# joystick_controller.net
KiCad netlist of a schematic drawn in EAGLE
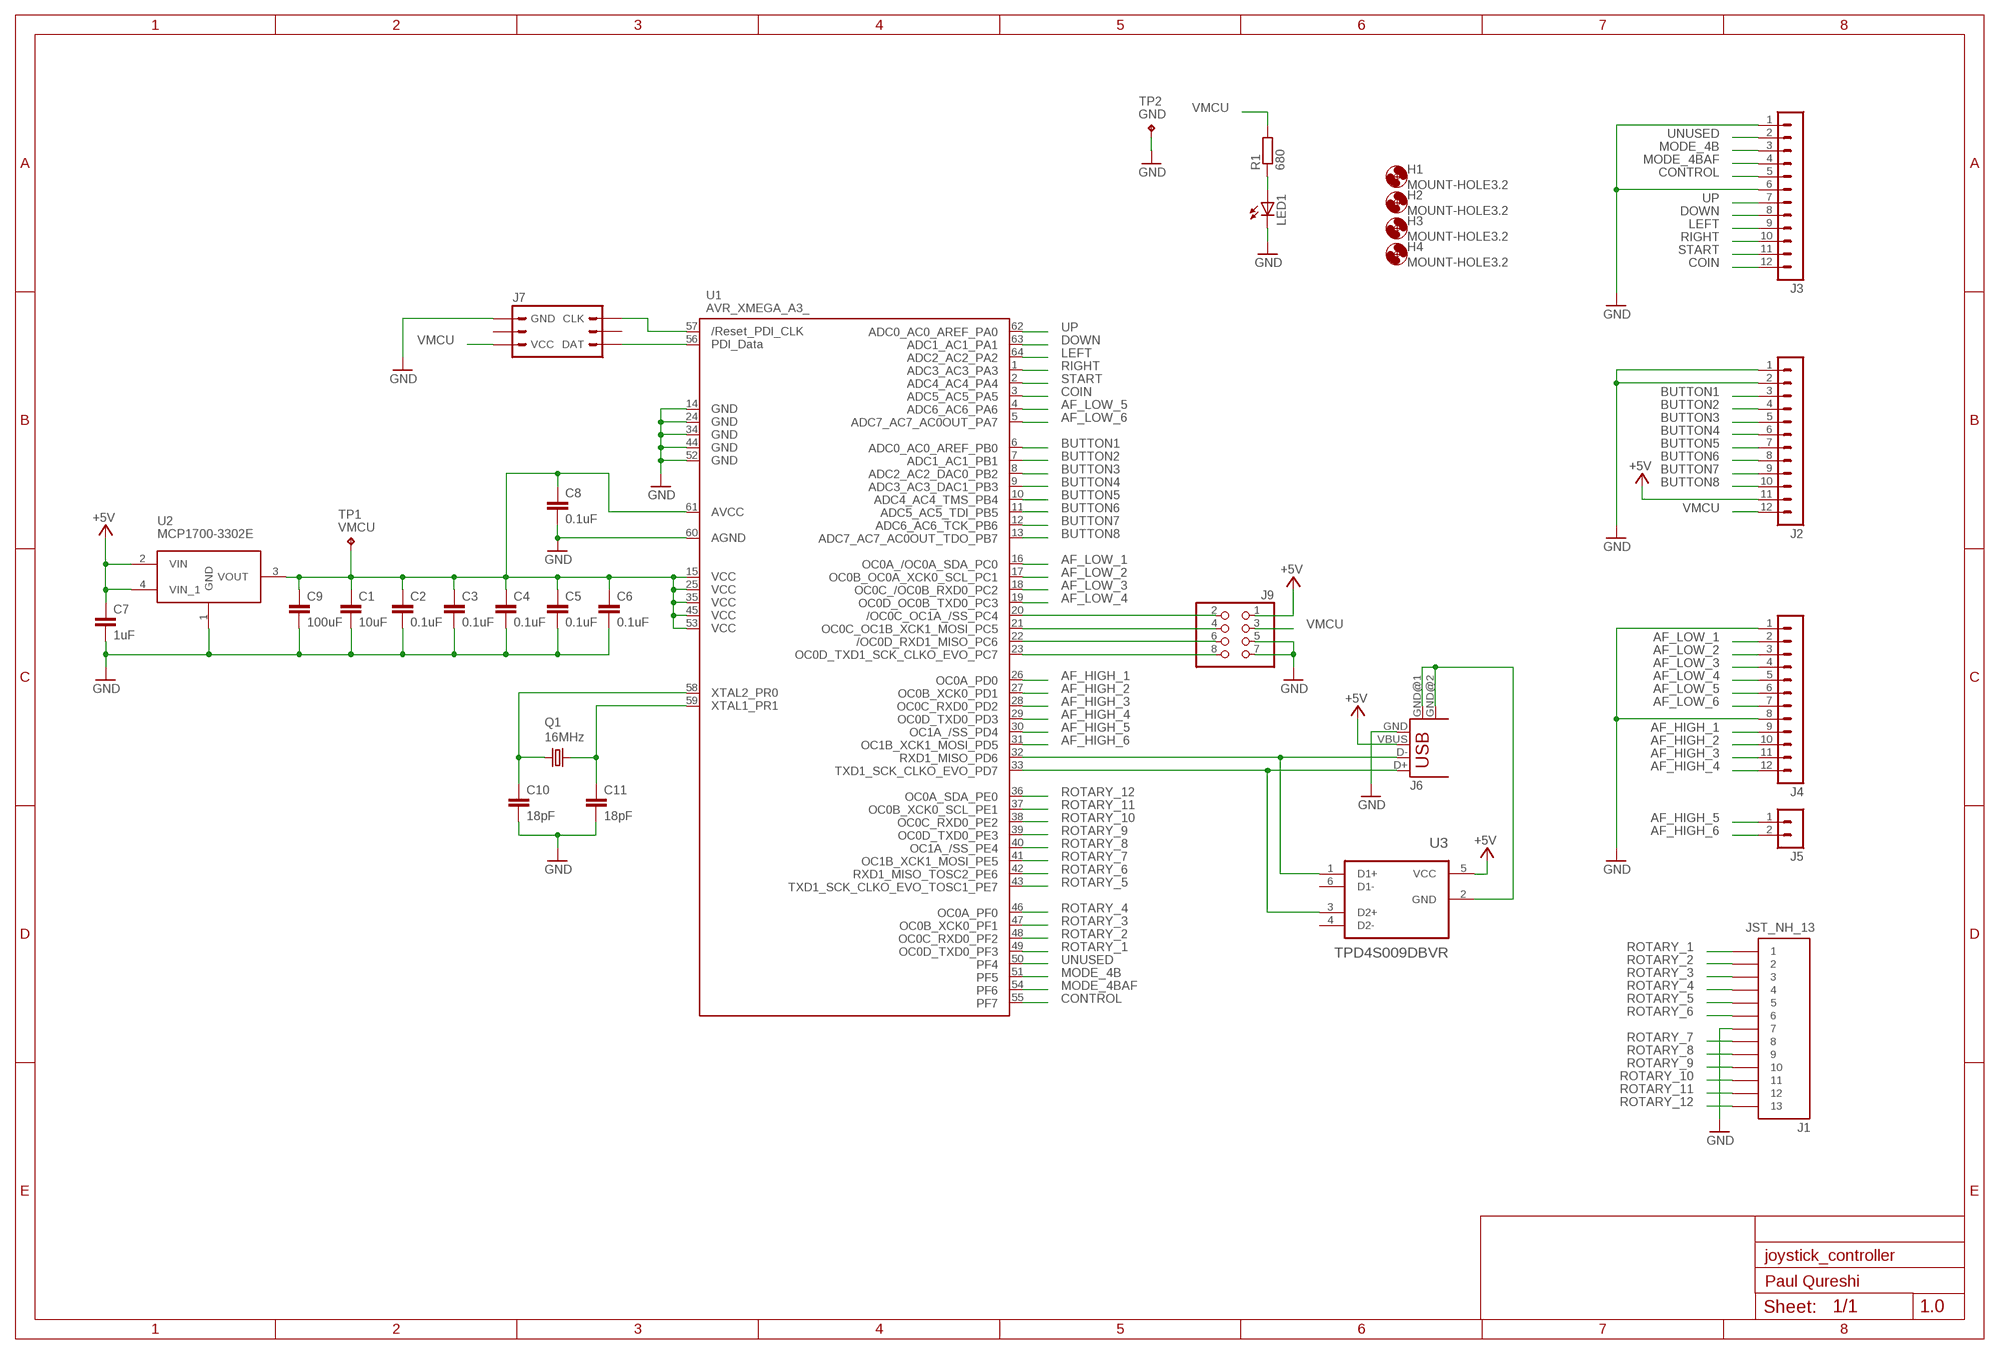
[diagram p0: schematic, sheet 1]

(export (version "E")
  (design (tool "Eeschema 10.0.6"))
  (components
    (comp (ref "C1")
      (value "10uF")
      (footprint "eagle-import:C0805")
      (libsource (lib "eagle-import") (part "C-EUC0805"))
    )
    (comp (ref "C2")
      (value "0.1uF")
      (footprint "eagle-import:C0805")
      (libsource (lib "eagle-import") (part "C-EUC0805"))
    )
    (comp (ref "C3")
      (value "0.1uF")
      (footprint "eagle-import:C0805")
      (libsource (lib "eagle-import") (part "C-EUC0805"))
    )
    (comp (ref "C4")
      (value "0.1uF")
      (footprint "eagle-import:C0805")
      (libsource (lib "eagle-import") (part "C-EUC0805"))
    )
    (comp (ref "C5")
      (value "0.1uF")
      (footprint "eagle-import:C0805")
      (libsource (lib "eagle-import") (part "C-EUC0805"))
    )
    (comp (ref "C6")
      (value "0.1uF")
      (footprint "eagle-import:C0805")
      (libsource (lib "eagle-import") (part "C-EUC0805"))
    )
    (comp (ref "C7")
      (value "1uF")
      (footprint "eagle-import:C0805")
      (libsource (lib "eagle-import") (part "C-EUC0805"))
    )
    (comp (ref "C8")
      (value "0.1uF")
      (footprint "eagle-import:C0805")
      (libsource (lib "eagle-import") (part "C-EUC0805"))
    )
    (comp (ref "C9")
      (value "100uF")
      (footprint "eagle-import:C1206")
      (libsource (lib "eagle-import") (part "C-EUC1206"))
    )
    (comp (ref "C10")
      (value "18pF")
      (footprint "eagle-import:C0805")
      (libsource (lib "eagle-import") (part "C-EUC0805"))
    )
    (comp (ref "C11")
      (value "18pF")
      (footprint "eagle-import:C0805")
      (libsource (lib "eagle-import") (part "C-EUC0805"))
    )
    (comp (ref "H1")
      (value "MOUNT-HOLE3.2")
      (footprint "eagle-import:3,2")
      (libsource (lib "eagle-import") (part "MOUNT-HOLE3.2"))
    )
    (comp (ref "H2")
      (value "MOUNT-HOLE3.2")
      (footprint "eagle-import:3,2")
      (libsource (lib "eagle-import") (part "MOUNT-HOLE3.2"))
    )
    (comp (ref "H3")
      (value "MOUNT-HOLE3.2")
      (footprint "eagle-import:3,2")
      (libsource (lib "eagle-import") (part "MOUNT-HOLE3.2"))
    )
    (comp (ref "H4")
      (value "MOUNT-HOLE3.2")
      (footprint "eagle-import:3,2")
      (libsource (lib "eagle-import") (part "MOUNT-HOLE3.2"))
    )
    (comp (ref "J1")
      (value "JST_NH_13")
      (footprint "eagle-import:JST_NH_13_RA")
      (libsource (lib "eagle-import") (part "JST_NH_13"))
    )
    (comp (ref "J2")
      (value "CON-3.5TERM-12")
      (footprint "eagle-import:CON-3.5TERM-12")
      (libsource (lib "eagle-import") (part "CON-3.5TERM-12"))
    )
    (comp (ref "J3")
      (value "CON-3.5TERM-12")
      (footprint "eagle-import:CON-3.5TERM-12")
      (libsource (lib "eagle-import") (part "CON-3.5TERM-12"))
    )
    (comp (ref "J4")
      (value "CON-3.5TERM-12")
      (footprint "eagle-import:CON-3.5TERM-12")
      (libsource (lib "eagle-import") (part "CON-3.5TERM-12"))
    )
    (comp (ref "J5")
      (value "CON-3.5TERM-2")
      (footprint "eagle-import:CON-3.5TERM-2")
      (libsource (lib "eagle-import") (part "CON-3.5TERM-2"))
    )
    (comp (ref "J6")
      (value "USB-B-H")
      (footprint "eagle-import:USB-B-H")
      (libsource (lib "eagle-import") (part "USB-B-H"))
    )
    (comp (ref "J7")
      (value "PDI_HEADER")
      (footprint "eagle-import:MA03-2")
      (libsource (lib "eagle-import") (part "PDI_HEADER"))
    )
    (comp (ref "J9")
      (value "PINHD-2X4")
      (footprint "eagle-import:2X04")
      (libsource (lib "eagle-import") (part "PINHD-2X4"))
    )
    (comp (ref "LED1")
      (value "LEDCHIP-LED0805")
      (footprint "eagle-import:CHIP-LED0805")
      (libsource (lib "eagle-import") (part "LEDCHIP-LED0805"))
    )
    (comp (ref "Q1")
      (value "16MHz")
      (footprint "eagle-import:HC49_S")
      (libsource (lib "eagle-import") (part "CRYSTALHC49S"))
    )
    (comp (ref "R1")
      (value "680")
      (footprint "eagle-import:R0805")
      (libsource (lib "eagle-import") (part "R-EU_R0805"))
    )
    (comp (ref "TP1")
      (value "VMCU")
      (footprint "eagle-import:HARWIN-S1751-46")
      (libsource (lib "eagle-import") (part "TEST_POINTS1751"))
    )
    (comp (ref "TP2")
      (value "GND")
      (footprint "eagle-import:HARWIN-S1751-46")
      (libsource (lib "eagle-import") (part "TEST_POINTS1751"))
    )
    (comp (ref "U1")
      (value "AVR_XMEGA_A3_")
      (footprint "eagle-import:TQFP64")
      (libsource (lib "eagle-import") (part "AVR_XMEGA_A3_"))
    )
    (comp (ref "U2")
      (value "MCP1700-3302E")
      (footprint "eagle-import:SOT150P400X160-4N")
      (fields (field (name "MPN") "MCP1700T-3302E/MB"))
      (libsource (lib "eagle-import") (part "MCP17-MCP1700T-3302E/MB"))
    )
    (comp (ref "U3")
      (value "TPD4S009DBVR")
      (footprint "eagle-import:SOT95P280X145-6N")
      (libsource (lib "eagle-import") (part "TPD4S009DBVR"))
    )
  )
  (nets
    (net (code "1") (name "+5V") (class "Default")
      (node (ref "C7") (pin "1") (pinfunction "1_1") (pintype "passive"))
      (node (ref "J2") (pin "11") (pinfunction "11_11") (pintype "passive"))
      (node (ref "J6") (pin "VBUS") (pinfunction "VBUS_VBUS") (pintype "bidirectional"))
      (node (ref "J9") (pin "1") (pinfunction "1_1") (pintype "passive"))
      (node (ref "U2") (pin "2") (pinfunction "VIN_2") (pintype "input"))
      (node (ref "U2") (pin "4") (pinfunction "VIN_1_4") (pintype "input"))
      (node (ref "U3") (pin "5") (pinfunction "VCC_5") (pintype "power_in"))
    )
    (net (code "2") (name "/AF_HIGH_1") (class "Default")
      (node (ref "J4") (pin "9") (pinfunction "9_9") (pintype "passive"))
      (node (ref "U1") (pin "26") (pinfunction "PD0_26") (pintype "bidirectional"))
    )
    (net (code "3") (name "/AF_HIGH_2") (class "Default")
      (node (ref "J4") (pin "10") (pinfunction "10_10") (pintype "passive"))
      (node (ref "U1") (pin "27") (pinfunction "PD1_27") (pintype "bidirectional"))
    )
    (net (code "4") (name "/AF_HIGH_3") (class "Default")
      (node (ref "J4") (pin "11") (pinfunction "11_11") (pintype "passive"))
      (node (ref "U1") (pin "28") (pinfunction "PD2_28") (pintype "bidirectional"))
    )
    (net (code "5") (name "/AF_HIGH_4") (class "Default")
      (node (ref "J4") (pin "12") (pinfunction "12_12") (pintype "passive"))
      (node (ref "U1") (pin "29") (pinfunction "PD3_29") (pintype "bidirectional"))
    )
    (net (code "6") (name "/AF_HIGH_5") (class "Default")
      (node (ref "J5") (pin "1") (pinfunction "1_1") (pintype "passive"))
      (node (ref "U1") (pin "30") (pinfunction "PD4_30") (pintype "bidirectional"))
    )
    (net (code "7") (name "/AF_HIGH_6") (class "Default")
      (node (ref "J5") (pin "2") (pinfunction "2_2") (pintype "passive"))
      (node (ref "U1") (pin "31") (pinfunction "PD5_31") (pintype "bidirectional"))
    )
    (net (code "8") (name "/AF_LOW_1") (class "Default")
      (node (ref "J4") (pin "2") (pinfunction "2_2") (pintype "passive"))
      (node (ref "U1") (pin "16") (pinfunction "PC0_16") (pintype "bidirectional"))
    )
    (net (code "9") (name "/AF_LOW_2") (class "Default")
      (node (ref "J4") (pin "3") (pinfunction "3_3") (pintype "passive"))
      (node (ref "U1") (pin "17") (pinfunction "PC1_17") (pintype "bidirectional"))
    )
    (net (code "10") (name "/AF_LOW_3") (class "Default")
      (node (ref "J4") (pin "4") (pinfunction "4_4") (pintype "passive"))
      (node (ref "U1") (pin "18") (pinfunction "PC2_18") (pintype "bidirectional"))
    )
    (net (code "11") (name "/AF_LOW_4") (class "Default")
      (node (ref "J4") (pin "5") (pinfunction "5_5") (pintype "passive"))
      (node (ref "U1") (pin "19") (pinfunction "PC3_19") (pintype "bidirectional"))
    )
    (net (code "12") (name "/AF_LOW_5") (class "Default")
      (node (ref "J4") (pin "6") (pinfunction "6_6") (pintype "passive"))
      (node (ref "U1") (pin "4") (pinfunction "PA6_4") (pintype "bidirectional"))
    )
    (net (code "13") (name "/AF_LOW_6") (class "Default")
      (node (ref "J4") (pin "7") (pinfunction "7_7") (pintype "passive"))
      (node (ref "U1") (pin "5") (pinfunction "PA7_5") (pintype "bidirectional"))
    )
    (net (code "14") (name "/BUTTON1") (class "Default")
      (node (ref "J2") (pin "3") (pinfunction "3_3") (pintype "passive"))
      (node (ref "U1") (pin "6") (pinfunction "PB0_6") (pintype "bidirectional"))
    )
    (net (code "15") (name "/BUTTON2") (class "Default")
      (node (ref "J2") (pin "4") (pinfunction "4_4") (pintype "passive"))
      (node (ref "U1") (pin "7") (pinfunction "PB1_7") (pintype "bidirectional"))
    )
    (net (code "16") (name "/BUTTON3") (class "Default")
      (node (ref "J2") (pin "5") (pinfunction "5_5") (pintype "passive"))
      (node (ref "U1") (pin "8") (pinfunction "PB2_8") (pintype "bidirectional"))
    )
    (net (code "17") (name "/BUTTON4") (class "Default")
      (node (ref "J2") (pin "6") (pinfunction "6_6") (pintype "passive"))
      (node (ref "U1") (pin "9") (pinfunction "PB3_9") (pintype "bidirectional"))
    )
    (net (code "18") (name "/BUTTON5") (class "Default")
      (node (ref "J2") (pin "7") (pinfunction "7_7") (pintype "passive"))
      (node (ref "U1") (pin "10") (pinfunction "PB4_10") (pintype "bidirectional"))
    )
    (net (code "19") (name "/BUTTON6") (class "Default")
      (node (ref "J2") (pin "8") (pinfunction "8_8") (pintype "passive"))
      (node (ref "U1") (pin "11") (pinfunction "PB5_11") (pintype "bidirectional"))
    )
    (net (code "20") (name "/BUTTON7") (class "Default")
      (node (ref "J2") (pin "9") (pinfunction "9_9") (pintype "passive"))
      (node (ref "U1") (pin "12") (pinfunction "PB6_12") (pintype "bidirectional"))
    )
    (net (code "21") (name "/BUTTON8") (class "Default")
      (node (ref "J2") (pin "10") (pinfunction "10_10") (pintype "passive"))
      (node (ref "U1") (pin "13") (pinfunction "PB7_13") (pintype "bidirectional"))
    )
    (net (code "22") (name "/COIN") (class "Default")
      (node (ref "J3") (pin "12") (pinfunction "12_12") (pintype "passive"))
      (node (ref "U1") (pin "3") (pinfunction "PA5_3") (pintype "bidirectional"))
    )
    (net (code "23") (name "/CONTROL") (class "Default")
      (node (ref "J3") (pin "5") (pinfunction "5_5") (pintype "passive"))
      (node (ref "U1") (pin "55") (pinfunction "PF7_55") (pintype "bidirectional"))
    )
    (net (code "24") (name "/DOWN") (class "Default")
      (node (ref "J3") (pin "8") (pinfunction "8_8") (pintype "passive"))
      (node (ref "U1") (pin "63") (pinfunction "PA1_63") (pintype "bidirectional"))
    )
    (net (code "25") (name "/LEFT") (class "Default")
      (node (ref "J3") (pin "9") (pinfunction "9_9") (pintype "passive"))
      (node (ref "U1") (pin "64") (pinfunction "PA2_64") (pintype "bidirectional"))
    )
    (net (code "26") (name "/MODE_4B") (class "Default")
      (node (ref "J3") (pin "3") (pinfunction "3_3") (pintype "passive"))
      (node (ref "U1") (pin "51") (pinfunction "PF5_51") (pintype "bidirectional"))
    )
    (net (code "27") (name "/MODE_4BAF") (class "Default")
      (node (ref "J3") (pin "4") (pinfunction "4_4") (pintype "passive"))
      (node (ref "U1") (pin "54") (pinfunction "PF6_54") (pintype "bidirectional"))
    )
    (net (code "28") (name "/RIGHT") (class "Default")
      (node (ref "J3") (pin "10") (pinfunction "10_10") (pintype "passive"))
      (node (ref "U1") (pin "1") (pinfunction "PA3_1") (pintype "bidirectional"))
    )
    (net (code "29") (name "/ROTARY_1") (class "Default")
      (node (ref "J1") (pin "1") (pinfunction "1_1") (pintype "passive"))
      (node (ref "U1") (pin "49") (pinfunction "PF3_49") (pintype "bidirectional"))
    )
    (net (code "30") (name "/ROTARY_2") (class "Default")
      (node (ref "J1") (pin "2") (pinfunction "2_2") (pintype "passive"))
      (node (ref "U1") (pin "48") (pinfunction "PF2_48") (pintype "bidirectional"))
    )
    (net (code "31") (name "/ROTARY_3") (class "Default")
      (node (ref "J1") (pin "3") (pinfunction "3_3") (pintype "passive"))
      (node (ref "U1") (pin "47") (pinfunction "PF1_47") (pintype "bidirectional"))
    )
    (net (code "32") (name "/ROTARY_4") (class "Default")
      (node (ref "J1") (pin "4") (pinfunction "4_4") (pintype "passive"))
      (node (ref "U1") (pin "46") (pinfunction "PF0_46") (pintype "bidirectional"))
    )
    (net (code "33") (name "/ROTARY_5") (class "Default")
      (node (ref "J1") (pin "5") (pinfunction "5_5") (pintype "passive"))
      (node (ref "U1") (pin "43") (pinfunction "PE7_43") (pintype "bidirectional"))
    )
    (net (code "34") (name "/ROTARY_6") (class "Default")
      (node (ref "J1") (pin "6") (pinfunction "6_6") (pintype "passive"))
      (node (ref "U1") (pin "42") (pinfunction "PE6_42") (pintype "bidirectional"))
    )
    (net (code "35") (name "/ROTARY_7") (class "Default")
      (node (ref "J1") (pin "8") (pinfunction "8_8") (pintype "passive"))
      (node (ref "U1") (pin "41") (pinfunction "PE5_41") (pintype "bidirectional"))
    )
    (net (code "36") (name "/ROTARY_8") (class "Default")
      (node (ref "J1") (pin "9") (pinfunction "9_9") (pintype "passive"))
      (node (ref "U1") (pin "40") (pinfunction "PE4_40") (pintype "bidirectional"))
    )
    (net (code "37") (name "/ROTARY_9") (class "Default")
      (node (ref "J1") (pin "10") (pinfunction "10_10") (pintype "passive"))
      (node (ref "U1") (pin "39") (pinfunction "PE3_39") (pintype "bidirectional"))
    )
    (net (code "38") (name "/ROTARY_10") (class "Default")
      (node (ref "J1") (pin "11") (pinfunction "11_11") (pintype "passive"))
      (node (ref "U1") (pin "38") (pinfunction "PE2_38") (pintype "bidirectional"))
    )
    (net (code "39") (name "/ROTARY_11") (class "Default")
      (node (ref "J1") (pin "12") (pinfunction "12_12") (pintype "passive"))
      (node (ref "U1") (pin "37") (pinfunction "PE1_37") (pintype "bidirectional"))
    )
    (net (code "40") (name "/ROTARY_12") (class "Default")
      (node (ref "J1") (pin "13") (pinfunction "13_13") (pintype "passive"))
      (node (ref "U1") (pin "36") (pinfunction "PE0_36") (pintype "bidirectional"))
    )
    (net (code "41") (name "/START") (class "Default")
      (node (ref "J3") (pin "11") (pinfunction "11_11") (pintype "passive"))
      (node (ref "U1") (pin "2") (pinfunction "PA4_2") (pintype "bidirectional"))
    )
    (net (code "42") (name "/UNUSED") (class "Default")
      (node (ref "J3") (pin "2") (pinfunction "2_2") (pintype "passive"))
      (node (ref "U1") (pin "50") (pinfunction "PF4_50") (pintype "bidirectional"))
    )
    (net (code "43") (name "/UP") (class "Default")
      (node (ref "J3") (pin "7") (pinfunction "7_7") (pintype "passive"))
      (node (ref "U1") (pin "62") (pinfunction "PA0_62") (pintype "bidirectional"))
    )
    (net (code "44") (name "/VMCU") (class "Default")
      (node (ref "C1") (pin "1") (pinfunction "1_1") (pintype "passive"))
      (node (ref "C2") (pin "1") (pinfunction "1_1") (pintype "passive"))
      (node (ref "C3") (pin "1") (pinfunction "1_1") (pintype "passive"))
      (node (ref "C4") (pin "1") (pinfunction "1_1") (pintype "passive"))
      (node (ref "C5") (pin "1") (pinfunction "1_1") (pintype "passive"))
      (node (ref "C6") (pin "1") (pinfunction "1_1") (pintype "passive"))
      (node (ref "C8") (pin "1") (pinfunction "1_1") (pintype "passive"))
      (node (ref "C9") (pin "1") (pinfunction "1_1") (pintype "passive"))
      (node (ref "J2") (pin "12") (pinfunction "12_12") (pintype "passive"))
      (node (ref "J7") (pin "2") (pinfunction "VCC_2") (pintype "passive"))
      (node (ref "J9") (pin "3") (pinfunction "3_3") (pintype "passive"))
      (node (ref "R1") (pin "2") (pinfunction "2_2") (pintype "passive"))
      (node (ref "TP1") (pin "P$1") (pinfunction "Q1_P$1") (pintype "passive"))
      (node (ref "U1") (pin "15") (pinfunction "VCC1_15") (pintype "bidirectional"))
      (node (ref "U1") (pin "25") (pinfunction "VCC2_25") (pintype "bidirectional"))
      (node (ref "U1") (pin "35") (pinfunction "VCC3_35") (pintype "bidirectional"))
      (node (ref "U1") (pin "45") (pinfunction "VCC4_45") (pintype "bidirectional"))
      (node (ref "U1") (pin "53") (pinfunction "VCC5_53") (pintype "bidirectional"))
      (node (ref "U1") (pin "61") (pinfunction "AVCC_61") (pintype "bidirectional"))
      (node (ref "U2") (pin "3") (pinfunction "VOUT_3") (pintype "output"))
    )
    (net (code "45") (name "GND") (class "Default")
      (node (ref "C1") (pin "2") (pinfunction "2_2") (pintype "passive"))
      (node (ref "C10") (pin "2") (pinfunction "2_2") (pintype "passive"))
      (node (ref "C11") (pin "2") (pinfunction "2_2") (pintype "passive"))
      (node (ref "C2") (pin "2") (pinfunction "2_2") (pintype "passive"))
      (node (ref "C3") (pin "2") (pinfunction "2_2") (pintype "passive"))
      (node (ref "C4") (pin "2") (pinfunction "2_2") (pintype "passive"))
      (node (ref "C5") (pin "2") (pinfunction "2_2") (pintype "passive"))
      (node (ref "C6") (pin "2") (pinfunction "2_2") (pintype "passive"))
      (node (ref "C7") (pin "2") (pinfunction "2_2") (pintype "passive"))
      (node (ref "C8") (pin "2") (pinfunction "2_2") (pintype "passive"))
      (node (ref "C9") (pin "2") (pinfunction "2_2") (pintype "passive"))
      (node (ref "J1") (pin "7") (pinfunction "7_7") (pintype "passive"))
      (node (ref "J2") (pin "1") (pinfunction "1_1") (pintype "passive"))
      (node (ref "J2") (pin "2") (pinfunction "2_2") (pintype "passive"))
      (node (ref "J3") (pin "1") (pinfunction "1_1") (pintype "passive"))
      (node (ref "J3") (pin "6") (pinfunction "6_6") (pintype "passive"))
      (node (ref "J4") (pin "1") (pinfunction "1_1") (pintype "passive"))
      (node (ref "J4") (pin "8") (pinfunction "8_8") (pintype "passive"))
      (node (ref "J6") (pin "GND") (pinfunction "GND_GND") (pintype "bidirectional"))
      (node (ref "J7") (pin "6") (pinfunction "GND_6") (pintype "passive"))
      (node (ref "J9") (pin "5") (pinfunction "5_5") (pintype "passive"))
      (node (ref "J9") (pin "7") (pinfunction "7_7") (pintype "passive"))
      (node (ref "LED1") (pin "C") (pinfunction "C_C") (pintype "passive"))
      (node (ref "TP2") (pin "P$1") (pinfunction "Q1_P$1") (pintype "passive"))
      (node (ref "U1") (pin "14") (pinfunction "GND1_14") (pintype "bidirectional"))
      (node (ref "U1") (pin "24") (pinfunction "GND2_24") (pintype "bidirectional"))
      (node (ref "U1") (pin "34") (pinfunction "GND3_34") (pintype "bidirectional"))
      (node (ref "U1") (pin "44") (pinfunction "GND4_44") (pintype "bidirectional"))
      (node (ref "U1") (pin "52") (pinfunction "GND5_52") (pintype "bidirectional"))
      (node (ref "U1") (pin "60") (pinfunction "AGND_60") (pintype "bidirectional"))
      (node (ref "U2") (pin "1") (pinfunction "GND_1") (pintype "power_in"))
    )
    (net (code "46") (name "Net-(J7-CLK)") (class "Default")
      (node (ref "J7") (pin "5") (pinfunction "CLK_5") (pintype "passive"))
      (node (ref "U1") (pin "57") (pinfunction "RESET_57") (pintype "bidirectional"))
    )
    (net (code "47") (name "Net-(J7-DAT)") (class "Default")
      (node (ref "J7") (pin "1") (pinfunction "DAT_1") (pintype "passive"))
      (node (ref "U1") (pin "56") (pinfunction "PDI_DATA_56") (pintype "bidirectional"))
    )
    (net (code "48") (name "Net-(LED1-PadA)") (class "Default")
      (node (ref "LED1") (pin "A") (pinfunction "A_A") (pintype "passive"))
      (node (ref "R1") (pin "1") (pinfunction "1_1") (pintype "passive"))
    )
    (net (code "49") (name "Net-(U1-PC4)") (class "Default")
      (node (ref "J9") (pin "2") (pinfunction "2_2") (pintype "passive"))
      (node (ref "U1") (pin "20") (pinfunction "PC4_20") (pintype "bidirectional"))
    )
    (net (code "50") (name "Net-(U1-PC5)") (class "Default")
      (node (ref "J9") (pin "4") (pinfunction "4_4") (pintype "passive"))
      (node (ref "U1") (pin "21") (pinfunction "PC5_21") (pintype "bidirectional"))
    )
    (net (code "51") (name "Net-(U1-PC6)") (class "Default")
      (node (ref "J9") (pin "6") (pinfunction "6_6") (pintype "passive"))
      (node (ref "U1") (pin "22") (pinfunction "PC6_22") (pintype "bidirectional"))
    )
    (net (code "52") (name "Net-(U1-PC7)") (class "Default")
      (node (ref "J9") (pin "8") (pinfunction "8_8") (pintype "passive"))
      (node (ref "U1") (pin "23") (pinfunction "PC7_23") (pintype "bidirectional"))
    )
    (net (code "53") (name "Net-(U1-PD6)") (class "Default")
      (node (ref "J6") (pin "D-") (pinfunction "D-_D-") (pintype "bidirectional"))
      (node (ref "U1") (pin "32") (pinfunction "PD6_32") (pintype "bidirectional"))
      (node (ref "U3") (pin "1") (pinfunction "D1+_1") (pintype "input"))
    )
    (net (code "54") (name "Net-(U1-PD7)") (class "Default")
      (node (ref "J6") (pin "D+") (pinfunction "D+_D+") (pintype "bidirectional"))
      (node (ref "U1") (pin "33") (pinfunction "PD7_33") (pintype "bidirectional"))
      (node (ref "U3") (pin "3") (pinfunction "D2+_3") (pintype "input"))
    )
    (net (code "55") (name "Net-(U1-PR0)") (class "Default")
      (node (ref "C10") (pin "1") (pinfunction "1_1") (pintype "passive"))
      (node (ref "Q1") (pin "1") (pinfunction "1_1") (pintype "passive"))
      (node (ref "U1") (pin "58") (pinfunction "PR0_58") (pintype "bidirectional"))
    )
    (net (code "56") (name "Net-(U1-PR1)") (class "Default")
      (node (ref "C11") (pin "1") (pinfunction "1_1") (pintype "passive"))
      (node (ref "Q1") (pin "2") (pinfunction "2_2") (pintype "passive"))
      (node (ref "U1") (pin "59") (pinfunction "PR1_59") (pintype "bidirectional"))
    )
    (net (code "57") (name "Net-(U3-GND)") (class "Default")
      (node (ref "J6") (pin "GND@1") (pinfunction "GND_GND@1") (pintype "bidirectional"))
      (node (ref "J6") (pin "GND@2") (pinfunction "GND_GND@2") (pintype "bidirectional"))
      (node (ref "U3") (pin "2") (pinfunction "GND_2") (pintype "passive"))
    )
    (net (code "58") (name "unconnected-(J7-NC-Pad3)") (class "Default")
      (node (ref "J7") (pin "3") (pinfunction "NC_3") (pintype "passive"))
    )
    (net (code "59") (name "unconnected-(J7-NC-Pad4)") (class "Default")
      (node (ref "J7") (pin "4") (pinfunction "NC_4") (pintype "passive"))
    )
    (net (code "60") (name "unconnected-(U3-D1--Pad6)") (class "Default")
      (node (ref "U3") (pin "6") (pinfunction "D1-_6") (pintype "input"))
    )
    (net (code "61") (name "unconnected-(U3-D2--Pad4)") (class "Default")
      (node (ref "U3") (pin "4") (pinfunction "D2-_4") (pintype "input"))
    )
  )
)
